# MCU.net
KiCad netlist of a schematic drawn in Altium Designer
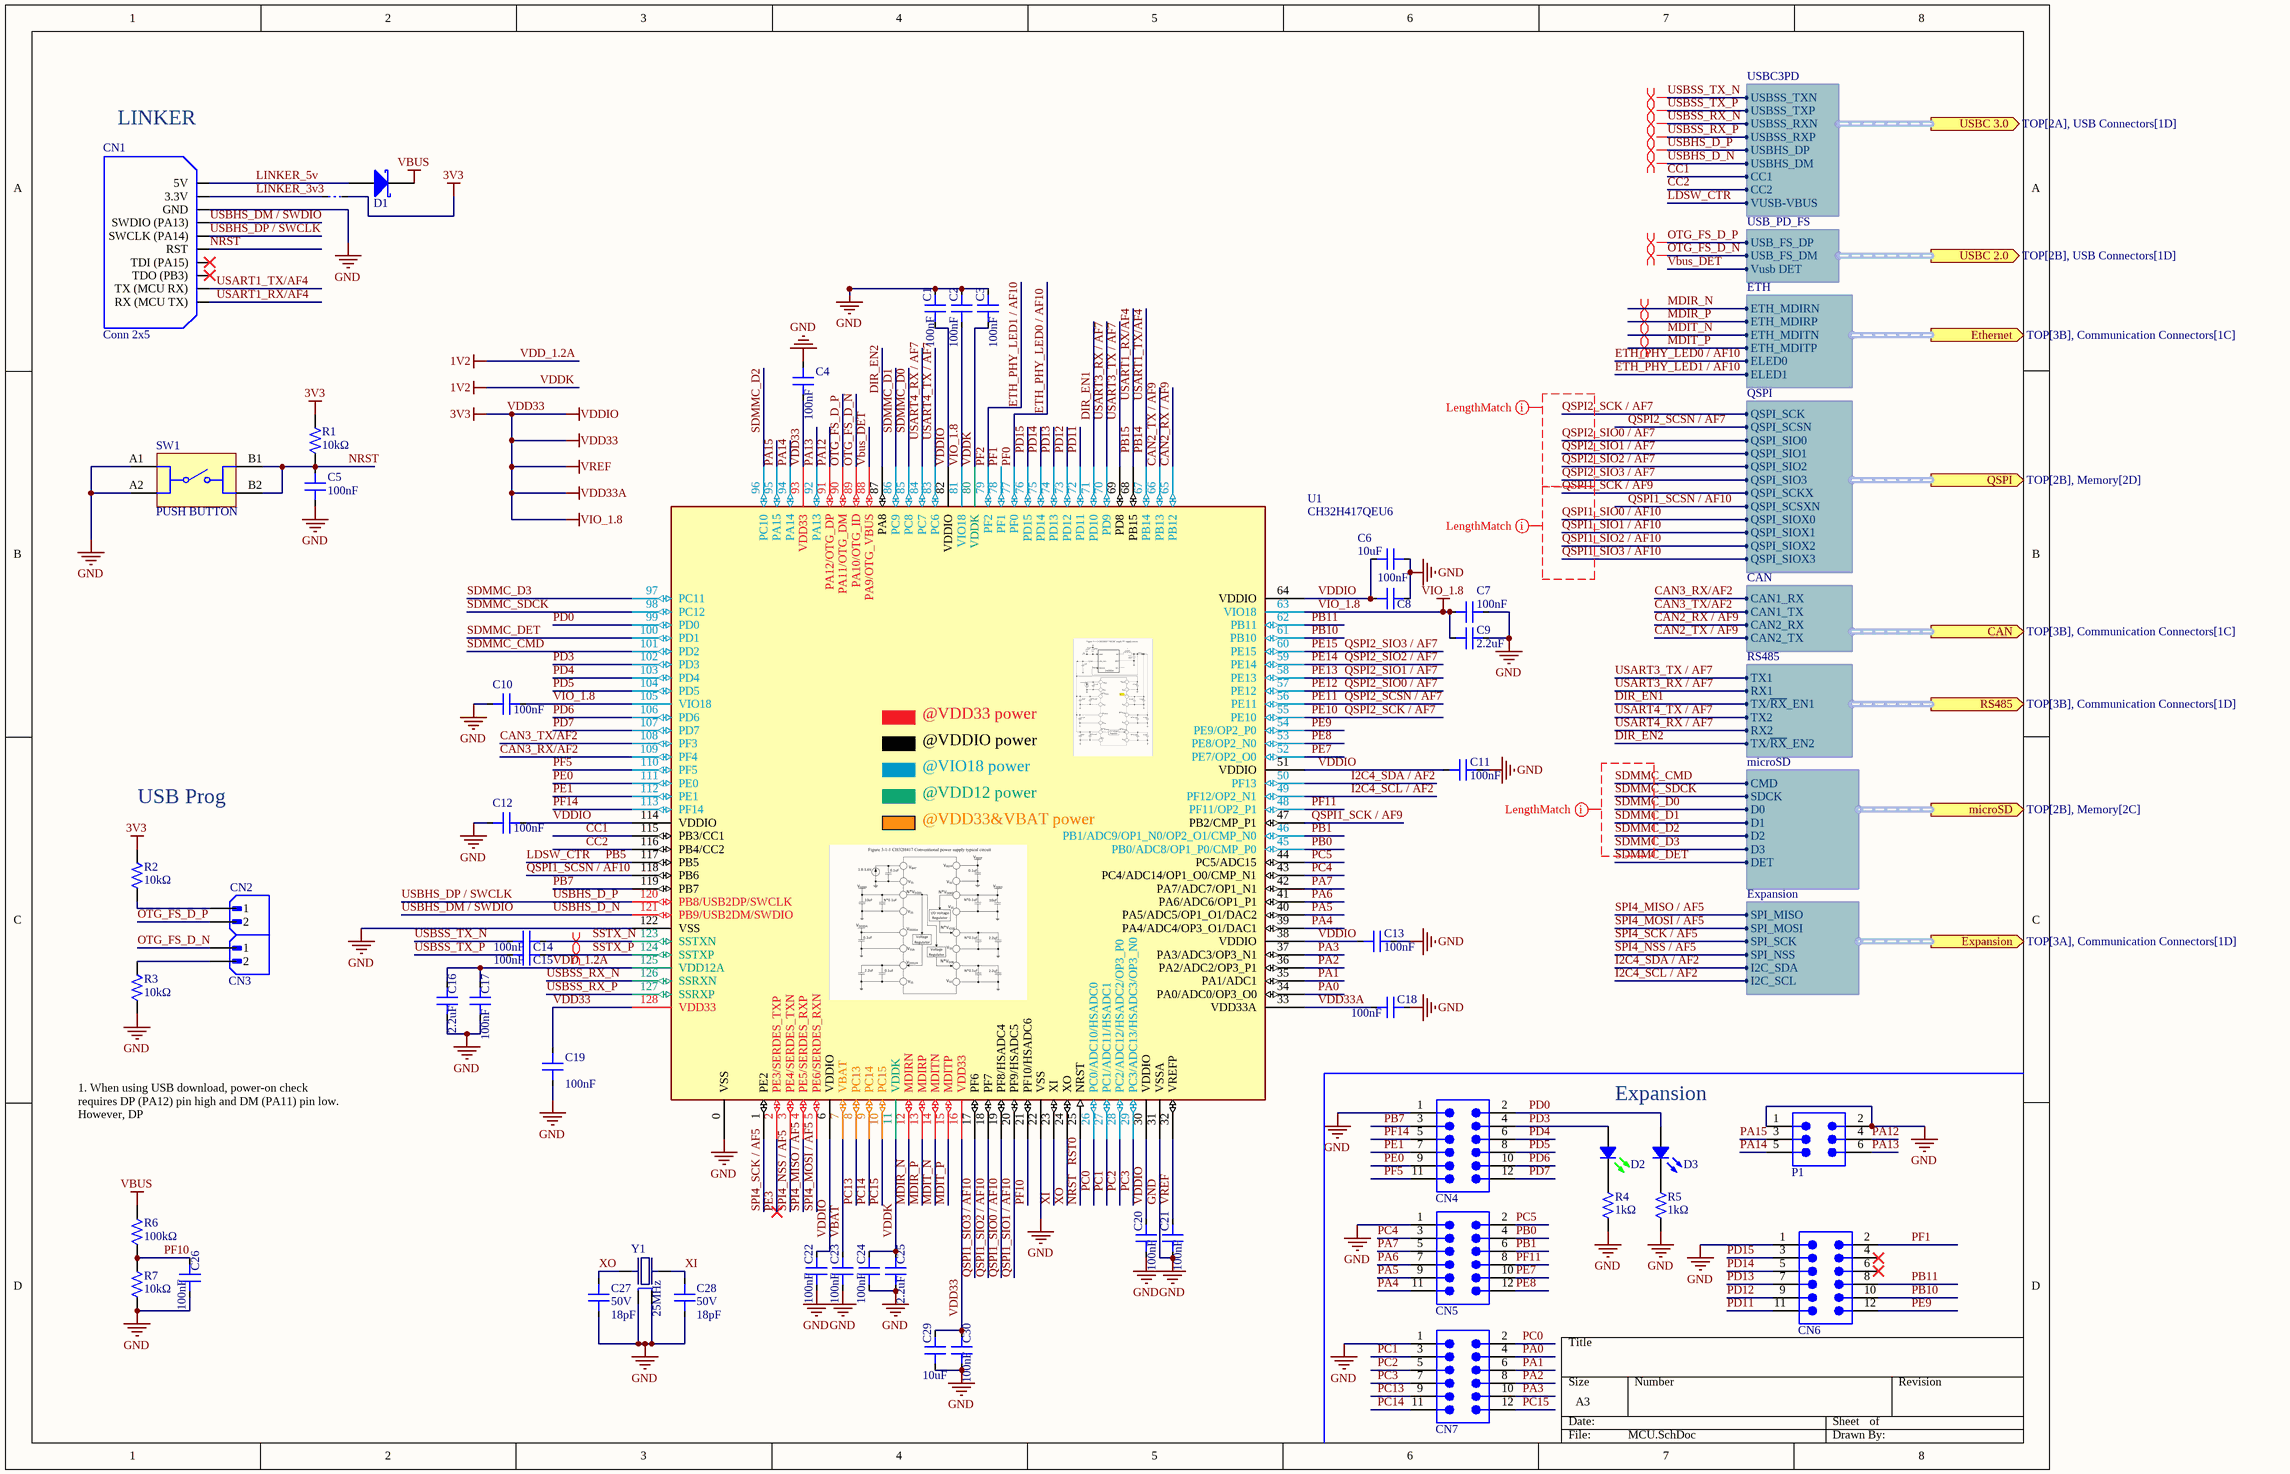
[diagram p0: MCU.SchDoc]

(export (version "E")
  (design (tool "Eeschema 10.0.6"))
  (components
    (comp (ref "C1")
      (value "CAP CER 100nF 50V X7R 0603")
      (footprint "C_0603")
      (description "100nF ±10% 50V Ceramic Capacitor X7R 0603")
      (fields
        (field (name "CAPACITANCE") "100nF")
        (field (name "MPN") "CC0603KRX7R9BB104")
        (field (name "LCSC PART #") "C14663")
      )
      (libsource (lib "Database_Libs_MICH_1") (part "CAP"))
    )
    (comp (ref "C2")
      (value "CAP CER 100nF 50V X7R 0603")
      (footprint "C_0603")
      (description "100nF ±10% 50V Ceramic Capacitor X7R 0603")
      (fields
        (field (name "CAPACITANCE") "100nF")
        (field (name "MPN") "CC0603KRX7R9BB104")
        (field (name "LCSC PART #") "C14663")
      )
      (libsource (lib "Database_Libs_MICH_1") (part "CAP"))
    )
    (comp (ref "C3")
      (value "CAP CER 100nF 50V X7R 0603")
      (footprint "C_0603")
      (description "100nF ±10% 50V Ceramic Capacitor X7R 0603")
      (fields
        (field (name "CAPACITANCE") "100nF")
        (field (name "MPN") "CC0603KRX7R9BB104")
        (field (name "LCSC PART #") "C14663")
      )
      (libsource (lib "Database_Libs_MICH_1") (part "CAP"))
    )
    (comp (ref "C4")
      (value "CAP CER 100nF 50V X7R 0603")
      (footprint "C_0603")
      (description "100nF ±10% 50V Ceramic Capacitor X7R 0603")
      (fields
        (field (name "CAPACITANCE") "100nF")
        (field (name "MPN") "CC0603KRX7R9BB104")
        (field (name "LCSC PART #") "C14663")
      )
      (libsource (lib "Database_Libs_MICH_1") (part "CAP"))
    )
    (comp (ref "C5")
      (value "CAP CER 100nF 50V X7R 0603")
      (footprint "C_0603")
      (description "100nF ±10% 50V Ceramic Capacitor X7R 0603")
      (fields
        (field (name "CAPACITANCE") "100nF")
        (field (name "MPN") "CC0603KRX7R9BB104")
        (field (name "LCSC PART #") "C14663")
      )
      (libsource (lib "Database_Libs_MICH_1") (part "CAP"))
    )
    (comp (ref "C6")
      (value "CAP CER 10uF 16V X7R 0805")
      (footprint "C_0805")
      (description "10uF ±10% 16V Ceramic Capacitor X7R 0805")
      (fields
        (field (name "CAPACITANCE") "10uF")
        (field (name "MPN") "CL21B106KOQNNNE")
        (field (name "LCSC PART #") "C95841")
      )
      (libsource (lib "Database_Libs_MICH_1") (part "CAP"))
    )
    (comp (ref "C7")
      (value "CAP CER 100nF 50V X7R 0603")
      (footprint "C_0603")
      (description "100nF ±10% 50V Ceramic Capacitor X7R 0603")
      (fields
        (field (name "CAPACITANCE") "100nF")
        (field (name "MPN") "CC0603KRX7R9BB104")
        (field (name "LCSC PART #") "C14663")
      )
      (libsource (lib "Database_Libs_MICH_1") (part "CAP"))
    )
    (comp (ref "C8")
      (value "CAP CER 100nF 50V X7R 0603")
      (footprint "C_0603")
      (description "100nF ±10% 50V Ceramic Capacitor X7R 0603")
      (fields
        (field (name "CAPACITANCE") "100nF")
        (field (name "MPN") "CC0603KRX7R9BB104")
        (field (name "LCSC PART #") "C14663")
      )
      (libsource (lib "Database_Libs_MICH_1") (part "CAP"))
    )
    (comp (ref "C9")
      (value "CAP CER 2.2uF 16V X5R 0603")
      (footprint "C_0603")
      (description "2.2uF ±10% 16V Ceramic Capacitor X5R 0603")
      (fields
        (field (name "CAPACITANCE") "2.2uF")
        (field (name "MPN") "CL10A225KO8NNNC")
        (field (name "LCSC PART #") "C23630")
      )
      (libsource (lib "Database_Libs_MICH_1") (part "CAP"))
    )
    (comp (ref "C10")
      (value "CAP CER 100nF 50V X7R 0603")
      (footprint "C_0603")
      (description "100nF ±10% 50V Ceramic Capacitor X7R 0603")
      (fields
        (field (name "CAPACITANCE") "100nF")
        (field (name "MPN") "CC0603KRX7R9BB104")
        (field (name "LCSC PART #") "C14663")
      )
      (libsource (lib "Database_Libs_MICH_1") (part "CAP"))
    )
    (comp (ref "C11")
      (value "CAP CER 100nF 50V X7R 0603")
      (footprint "C_0603")
      (description "100nF ±10% 50V Ceramic Capacitor X7R 0603")
      (fields
        (field (name "CAPACITANCE") "100nF")
        (field (name "MPN") "CC0603KRX7R9BB104")
        (field (name "LCSC PART #") "C14663")
      )
      (libsource (lib "Database_Libs_MICH_1") (part "CAP"))
    )
    (comp (ref "C12")
      (value "CAP CER 100nF 50V X7R 0603")
      (footprint "C_0603")
      (description "100nF ±10% 50V Ceramic Capacitor X7R 0603")
      (fields
        (field (name "CAPACITANCE") "100nF")
        (field (name "MPN") "CC0603KRX7R9BB104")
        (field (name "LCSC PART #") "C14663")
      )
      (libsource (lib "Database_Libs_MICH_1") (part "CAP"))
    )
    (comp (ref "C13")
      (value "CAP CER 100nF 50V X7R 0603")
      (footprint "C_0603")
      (description "100nF ±10% 50V Ceramic Capacitor X7R 0603")
      (fields
        (field (name "CAPACITANCE") "100nF")
        (field (name "MPN") "CC0603KRX7R9BB104")
        (field (name "LCSC PART #") "C14663")
      )
      (libsource (lib "Database_Libs_MICH_1") (part "CAP"))
    )
    (comp (ref "C14")
      (value "CAP CER 100nF 50V X7R 0603")
      (footprint "C_0603")
      (description "100nF ±10% 50V Ceramic Capacitor X7R 0603")
      (fields
        (field (name "CAPACITANCE") "100nF")
        (field (name "LCSC PART #") "C14663")
        (field (name "MANUFACTURER") "YAGEO")
      )
      (libsource (lib "Database_Libs_MICH_1") (part "CAP"))
    )
    (comp (ref "C15")
      (value "CAP CER 100nF 50V X7R 0603")
      (footprint "C_0603")
      (description "100nF ±10% 50V Ceramic Capacitor X7R 0603")
      (fields
        (field (name "CAPACITANCE") "100nF")
        (field (name "LCSC PART #") "C14663")
        (field (name "MANUFACTURER") "YAGEO")
      )
      (libsource (lib "Database_Libs_MICH_1") (part "CAP"))
    )
    (comp (ref "C16")
      (value "CAP CER 2.2uF 16V X5R 0603")
      (footprint "C_0603")
      (description "2.2uF ±10% 16V Ceramic Capacitor X5R 0603")
      (fields
        (field (name "CAPACITANCE") "2.2uF")
        (field (name "MPN") "CL10A225KO8NNNC")
        (field (name "LCSC PART #") "C23630")
      )
      (libsource (lib "Database_Libs_MICH_1") (part "CAP"))
    )
    (comp (ref "C17")
      (value "CAP CER 100nF 50V X7R 0603")
      (footprint "C_0603")
      (description "100nF ±10% 50V Ceramic Capacitor X7R 0603")
      (fields
        (field (name "CAPACITANCE") "100nF")
        (field (name "MPN") "CC0603KRX7R9BB104")
        (field (name "LCSC PART #") "C14663")
      )
      (libsource (lib "Database_Libs_MICH_1") (part "CAP"))
    )
    (comp (ref "C18")
      (value "CAP CER 100nF 50V X7R 0603")
      (footprint "C_0603")
      (description "100nF ±10% 50V Ceramic Capacitor X7R 0603")
      (fields
        (field (name "CAPACITANCE") "100nF")
        (field (name "MPN") "CC0603KRX7R9BB104")
        (field (name "LCSC PART #") "C14663")
      )
      (libsource (lib "Database_Libs_MICH_1") (part "CAP"))
    )
    (comp (ref "C19")
      (value "CAP CER 100nF 50V X7R 0603")
      (footprint "C_0603")
      (description "100nF ±10% 50V Ceramic Capacitor X7R 0603")
      (fields
        (field (name "CAPACITANCE") "100nF")
        (field (name "MPN") "CC0603KRX7R9BB104")
        (field (name "LCSC PART #") "C14663")
      )
      (libsource (lib "Database_Libs_MICH_1") (part "CAP"))
    )
    (comp (ref "C20")
      (value "CAP CER 100nF 50V X7R 0603")
      (footprint "C_0603")
      (description "100nF ±10% 50V Ceramic Capacitor X7R 0603")
      (fields
        (field (name "CAPACITANCE") "100nF")
        (field (name "MPN") "CC0603KRX7R9BB104")
        (field (name "LCSC PART #") "C14663")
      )
      (libsource (lib "Database_Libs_MICH_1") (part "CAP"))
    )
    (comp (ref "C21")
      (value "CAP CER 100nF 50V X7R 0603")
      (footprint "C_0603")
      (description "100nF ±10% 50V Ceramic Capacitor X7R 0603")
      (fields
        (field (name "CAPACITANCE") "100nF")
        (field (name "MPN") "CC0603KRX7R9BB104")
        (field (name "LCSC PART #") "C14663")
      )
      (libsource (lib "Database_Libs_MICH_1") (part "CAP"))
    )
    (comp (ref "C22")
      (value "CAP CER 100nF 50V X7R 0603")
      (footprint "C_0603")
      (description "100nF ±10% 50V Ceramic Capacitor X7R 0603")
      (fields
        (field (name "CAPACITANCE") "100nF")
        (field (name "MPN") "CC0603KRX7R9BB104")
        (field (name "LCSC PART #") "C14663")
      )
      (libsource (lib "Database_Libs_MICH_1") (part "CAP"))
    )
    (comp (ref "C23")
      (value "CAP CER 100nF 50V X7R 0603")
      (footprint "C_0603")
      (description "100nF ±10% 50V Ceramic Capacitor X7R 0603")
      (fields
        (field (name "CAPACITANCE") "100nF")
        (field (name "MPN") "CC0603KRX7R9BB104")
        (field (name "LCSC PART #") "C14663")
      )
      (libsource (lib "Database_Libs_MICH_1") (part "CAP"))
    )
    (comp (ref "C24")
      (value "CAP CER 100nF 50V X7R 0603")
      (footprint "C_0603")
      (description "100nF ±10% 50V Ceramic Capacitor X7R 0603")
      (fields
        (field (name "CAPACITANCE") "100nF")
        (field (name "MPN") "CC0603KRX7R9BB104")
        (field (name "LCSC PART #") "C14663")
      )
      (libsource (lib "Database_Libs_MICH_1") (part "CAP"))
    )
    (comp (ref "C25")
      (value "CAP CER 2.2uF 16V X5R 0603")
      (footprint "C_0603")
      (description "2.2uF ±10% 16V Ceramic Capacitor X5R 0603")
      (fields
        (field (name "CAPACITANCE") "2.2uF")
        (field (name "MPN") "CL10A225KO8NNNC")
        (field (name "LCSC PART #") "C23630")
      )
      (libsource (lib "Database_Libs_MICH_1") (part "CAP"))
    )
    (comp (ref "C26")
      (value "CAP CER 100nF 50V X7R 0603")
      (footprint "C_0603")
      (description "100nF ±10% 50V Ceramic Capacitor X7R 0603")
      (fields
        (field (name "CAPACITANCE") "100nF")
        (field (name "MPN") "CC0603KRX7R9BB104")
        (field (name "LCSC PART #") "C14663")
      )
      (libsource (lib "Database_Libs_MICH_1") (part "CAP"))
    )
    (comp (ref "C27")
      (value "CAP CER 18pF 50V C0G 0603")
      (footprint "C_0603")
      (description "18pF ±5% 50V Ceramic Capacitor C0G 0603")
      (fields
        (field (name "VOLTAGE RATING") "50V")
        (field (name "CAPACITANCE") "18pF")
        (field (name "LCSC PART #") "C1647")
        (field (name "MANUFACTURER") "Samsung Electro-Mechanics")
      )
      (libsource (lib "Database_Libs_MICH_1") (part "CAP"))
    )
    (comp (ref "C28")
      (value "CAP CER 18pF 50V C0G 0603")
      (footprint "C_0603")
      (description "18pF ±5% 50V Ceramic Capacitor C0G 0603")
      (fields
        (field (name "VOLTAGE RATING") "50V")
        (field (name "CAPACITANCE") "18pF")
        (field (name "LCSC PART #") "C1647")
        (field (name "MANUFACTURER") "Samsung Electro-Mechanics")
      )
      (libsource (lib "Database_Libs_MICH_1") (part "CAP"))
    )
    (comp (ref "C29")
      (value "CAP CER 10uF 16V X7R 0805")
      (footprint "C_0805")
      (description "10uF ±10% 16V Ceramic Capacitor X7R 0805")
      (fields
        (field (name "CAPACITANCE") "10uF")
        (field (name "MPN") "CL21B106KOQNNNE")
        (field (name "LCSC PART #") "C95841")
      )
      (libsource (lib "Database_Libs_MICH_1") (part "CAP"))
    )
    (comp (ref "C30")
      (value "CAP CER 100nF 50V X7R 0603")
      (footprint "C_0603")
      (description "100nF ±10% 50V Ceramic Capacitor X7R 0603")
      (fields
        (field (name "CAPACITANCE") "100nF")
        (field (name "MPN") "CC0603KRX7R9BB104")
        (field (name "LCSC PART #") "C14663")
      )
      (libsource (lib "Database_Libs_MICH_1") (part "CAP"))
    )
    (comp (ref "CN1")
      (value "Conn 2x5")
      (footprint "IDC_2x5P_2.54MM_TH")
      (description "CONN For WCH LINKE Debugger")
      (libsource (lib "MI_Personal_special") (part "WCH LINKE Debugger connector"))
    )
    (comp (ref "CN2")
      (value "CONN HEADER 2POS 2.54mm SINGLE ROW TH")
      (footprint "HEADER_M_2P_2.54MM_TH")
      (fields
        (field (name "MPN") "PZ254V-11-02P")
        (field (name "LCSC PART #") "C492401")
        (field (name "MANUFACTURER") "XFCN")
      )
      (libsource (lib "Database_Libs_MICH_1") (part "CONN_2"))
    )
    (comp (ref "CN3")
      (value "CONN HEADER 2POS 2.54mm SINGLE ROW TH")
      (footprint "HEADER_M_2P_2.54MM_TH")
      (fields
        (field (name "MPN") "PZ254V-11-02P")
        (field (name "LCSC PART #") "C492401")
        (field (name "MANUFACTURER") "XFCN")
      )
      (libsource (lib "Database_Libs_MICH_1") (part "CONN_2"))
    )
    (comp (ref "CN4")
      (value "CONN HEADER 12POS 2.54mm DUAL ROW TH")
      (footprint "HEADER_M_2x6P_2.54MM_TH")
      (description "Pin Header 12 Position 2.54mm Pitch Dual Row Through Hole -40℃~+105℃")
      (fields (field (name "MPN") "ZX-PZ2.54-2-6PZZ") (field (name "LCSC PART #") "C7501277"))
      (libsource (lib "Database_Libs_MICH_1") (part "CONN_2X6"))
    )
    (comp (ref "CN5")
      (value "CONN HEADER 12POS 2.54mm DUAL ROW TH")
      (footprint "HEADER_M_2x6P_2.54MM_TH")
      (description "Pin Header 12 Position 2.54mm Pitch Dual Row Through Hole -40℃~+105℃")
      (fields (field (name "MPN") "ZX-PZ2.54-2-6PZZ") (field (name "LCSC PART #") "C7501277"))
      (libsource (lib "Database_Libs_MICH_1") (part "CONN_2X6"))
    )
    (comp (ref "CN6")
      (value "CONN HEADER 12POS 2.54mm DUAL ROW TH")
      (footprint "HEADER_M_2x6P_2.54MM_TH")
      (description "Pin Header 12 Position 2.54mm Pitch Dual Row Through Hole -40℃~+105℃")
      (fields (field (name "MPN") "ZX-PZ2.54-2-6PZZ") (field (name "LCSC PART #") "C7501277"))
      (libsource (lib "Database_Libs_MICH_1") (part "CONN_2X6"))
    )
    (comp (ref "CN7")
      (value "CONN HEADER 12POS 2.54mm DUAL ROW TH")
      (footprint "HEADER_M_2x6P_2.54MM_TH")
      (description "Pin Header 12 Position 2.54mm Pitch Dual Row Through Hole -40℃~+105℃")
      (fields (field (name "MPN") "ZX-PZ2.54-2-6PZZ") (field (name "LCSC PART #") "C7501277"))
      (libsource (lib "Database_Libs_MICH_1") (part "CONN_2X6"))
    )
    (comp (ref "D1")
      (value "DIODE SCHOTTKY 40V SOD-323")
      (footprint "SOD323")
      (description "Diode 40V 1A Surface Mount SOD-323")
      (fields (field (name "MPN") "1N5819WS") (field (name "LCSC PART #") "C191023"))
      (libsource (lib "Database_Libs_MICH_1") (part "DIODE_SCHOTTKY"))
    )
    (comp (ref "D2")
      (value "LED EMERALD GREEN WATER CLEAR 0603 SMD")
      (footprint "LED_0603")
      (description "Emerald Green 525nm LED Indication - Discrete 3.3V 0603")
      (fields (field (name "MPN") "XL-1608UGC-04") (field (name "LCSC PART #") "C965804"))
      (libsource (lib "Database_Libs_MICH_1") (part "LED_EMERALD GREEN"))
    )
    (comp (ref "D3")
      (value "LED BLUE WATER CLEAR 0603 SMD")
      (footprint "LED_0603")
      (description "Blue 470nm LED Indication - Discrete 3.3V 0603")
      (fields (field (name "MPN") "XL-1608UBC-04") (field (name "LCSC PART #") "C965807"))
      (libsource (lib "Database_Libs_MICH_1") (part "LED_BLUE"))
    )
    (comp (ref "J1")
      (value "JUMPER SMD")
      (footprint "JUMPER SMD 3X1.5 mm")
      (libsource (lib "MI_Personal_special") (part "JUMPER SMD"))
    )
    (comp (ref "P1")
      (value "CONN SOCKET 6POS 2.54mm DUAL ROW TH")
      (footprint "HEADER_F_2x3P_2.54MM_TH")
      (description "Female Header 6 Position 2.54mm Pitch Dual Row Through Hole")
      (fields (field (name "MPN") "PM254V-12-06-H85") (field (name "LCSC PART #") "C541853"))
      (libsource (lib "Database_Libs_MICH_1") (part "CONN_2x3"))
    )
    (comp (ref "R1")
      (value "RES 10kΩ ±1% 100mW 0603")
      (footprint "R_0603")
      (description "10kΩ ±1% 100mW 0603 Thick Film Resistor")
      (fields
        (field (name "RESISTANCE") "10kΩ")
        (field (name "MPN") "0603WAF1002T5E")
        (field (name "POWER") "100mW")
      )
      (libsource (lib "Database_Libs_MICH_1") (part "RES"))
    )
    (comp (ref "R2")
      (value "RES 10kΩ ±1% 100mW 0603")
      (footprint "R_0603")
      (description "10kΩ ±1% 100mW 0603 Thick Film Resistor")
      (fields
        (field (name "RESISTANCE") "10kΩ")
        (field (name "MPN") "0603WAF1002T5E")
        (field (name "POWER") "100mW")
      )
      (libsource (lib "Database_Libs_MICH_1") (part "RES"))
    )
    (comp (ref "R3")
      (value "RES 10kΩ ±1% 100mW 0603")
      (footprint "R_0603")
      (description "10kΩ ±1% 100mW 0603 Thick Film Resistor")
      (fields
        (field (name "RESISTANCE") "10kΩ")
        (field (name "MPN") "0603WAF1002T5E")
        (field (name "POWER") "100mW")
      )
      (libsource (lib "Database_Libs_MICH_1") (part "RES"))
    )
    (comp (ref "R4")
      (value "RES 1kΩ ±1% 100mW 0603")
      (footprint "R_0603")
      (description "1kΩ ±1% 100mW 0603 Thick Film Resistor")
      (fields
        (field (name "RESISTANCE") "1kΩ")
        (field (name "MPN") "0603WAF1001T5E")
        (field (name "POWER") "100mW")
      )
      (libsource (lib "Database_Libs_MICH_1") (part "RES"))
    )
    (comp (ref "R5")
      (value "RES 1kΩ ±1% 100mW 0603")
      (footprint "R_0603")
      (description "1kΩ ±1% 100mW 0603 Thick Film Resistor")
      (fields
        (field (name "RESISTANCE") "1kΩ")
        (field (name "MPN") "0603WAF1001T5E")
        (field (name "POWER") "100mW")
      )
      (libsource (lib "Database_Libs_MICH_1") (part "RES"))
    )
    (comp (ref "R6")
      (value "RES 100kΩ ±1% 100mW 0603")
      (footprint "R_0603")
      (description "100kΩ ±1% 100mW 0603 Thick Film Resistor")
      (fields
        (field (name "RESISTANCE") "100kΩ")
        (field (name "LCSC PART #") "C25803")
        (field (name "MPN") "0603WAF1003T5E")
      )
      (libsource (lib "Database_Libs_MICH_1") (part "RES"))
    )
    (comp (ref "R7")
      (value "RES 10kΩ ±1% 100mW 0603")
      (footprint "R_0603")
      (description "10kΩ ±1% 100mW 0603 Thick Film Resistor")
      (fields
        (field (name "RESISTANCE") "10kΩ")
        (field (name "MPN") "0603WAF1002T5E")
        (field (name "POWER") "100mW")
      )
      (libsource (lib "Database_Libs_MICH_1") (part "RES"))
    )
    (comp (ref "SW1")
      (value "PUSH BUTTON")
      (footprint "Tact Switch 6X6X9.5MM")
      (description "SWITCH PUSH BUTTON 2X2 6X6X9.5MM")
      (libsource (lib "MI_Personal_special") (part "SH-6X6X8H-CJ"))
    )
    (comp (ref "U1")
      (value "CH32H417QEU6")
      (footprint "QFN128_12.3X12.3")
      (description "RISC-V FPU HD-MCU, 384MHz, USB3.0 & PD, 100M Ethernet, DVP, SDMMC, QSPI, OPA, ADC, DAC")
      (libsource (lib "DHXXXSCH") (part "CH32H417QET6"))
    )
    (comp (ref "Y1")
      (value "CRYSTAL 25MHz 12pF SMD")
      (footprint "XTAL_SMD3225-4P")
      (description "Crystal 25MHz ±10ppm 12pF SMD3225-4P")
      (fields
        (field (name "FREQUENCY") "25MHz")
        (field (name "MPN") "X322525MOB4SI")
        (field (name "LCSC PART #") "C9006")
      )
      (libsource (lib "Database_Libs_MICH_1") (part "XTAL-4P"))
    )
  )
  (nets
    (net (code "9") (name "/CAN2_RX {slash} AF9") (class "Default")
      (node (ref "U1") (pin "65") (pinfunction "PB12_65") (pintype "bidirectional"))
    )
    (net (code "10") (name "/CAN2_TX {slash} AF9") (class "Default")
      (node (ref "U1") (pin "66") (pinfunction "PB13_66") (pintype "bidirectional"))
    )
    (net (code "11") (name "/CAN3_RX{slash}AF2") (class "Default")
      (node (ref "U1") (pin "109") (pinfunction "PF4_109") (pintype "bidirectional"))
    )
    (net (code "12") (name "/CAN3_TX{slash}AF2") (class "Default")
      (node (ref "U1") (pin "108") (pinfunction "PF3_108") (pintype "bidirectional"))
    )
    (net (code "13") (name "/CC1") (class "Default")
      (node (ref "U1") (pin "115") (pinfunction "PB3/CC1_115") (pintype "bidirectional"))
    )
    (net (code "14") (name "/CC2") (class "Default")
      (node (ref "U1") (pin "116") (pinfunction "PB4/CC2_116") (pintype "bidirectional"))
    )
    (net (code "15") (name "/DIR_EN1") (class "Default")
      (node (ref "U1") (pin "71") (pinfunction "PD10_71") (pintype "bidirectional"))
    )
    (net (code "16") (name "/DIR_EN2") (class "Default")
      (node (ref "U1") (pin "87") (pinfunction "PA8_87") (pintype "bidirectional"))
    )
    (net (code "17") (name "/ETH_PHY_LED0 {slash} AF10") (class "Default")
      (node (ref "U1") (pin "77") (pinfunction "PF0_77") (pintype "bidirectional"))
    )
    (net (code "18") (name "/ETH_PHY_LED1 {slash} AF10") (class "Default")
      (node (ref "U1") (pin "79") (pinfunction "PF2_79") (pintype "bidirectional"))
    )
    (net (code "19") (name "/I2C4_SCL {slash} AF2") (class "Default")
      (node (ref "U1") (pin "49") (pinfunction "PF12/OP2_N1_49") (pintype "bidirectional"))
    )
    (net (code "20") (name "/I2C4_SDA {slash} AF2") (class "Default")
      (node (ref "U1") (pin "50") (pinfunction "PF13_50") (pintype "bidirectional"))
    )
    (net (code "21") (name "/LDSW_CTR") (class "Default")
      (node (ref "U1") (pin "117") (pinfunction "PB5_117") (pintype "bidirectional"))
    )
    (net (code "22") (name "/LINKER_3v3") (class "Default")
      (node (ref "CN1") (pin "3") (pinfunction "3.3V_3") (pintype "passive"))
      (node (ref "J1") (pin "2") (pinfunction "G_2") (pintype "passive"))
    )
    (net (code "23") (name "/LINKER_5v") (class "Default")
      (node (ref "CN1") (pin "1") (pinfunction "5V_1") (pintype "passive"))
      (node (ref "D1") (pin "1") (pinfunction "A_1") (pintype "passive"))
    )
    (net (code "24") (name "/MDIR_N") (class "Default")
      (node (ref "U1") (pin "12") (pinfunction "MDIRN_12") (pintype "bidirectional"))
    )
    (net (code "25") (name "/MDIR_P") (class "Default")
      (node (ref "U1") (pin "13") (pinfunction "MDIRP_13") (pintype "bidirectional"))
    )
    (net (code "26") (name "/MDIT_N") (class "Default")
      (node (ref "U1") (pin "14") (pinfunction "MDITN_14") (pintype "bidirectional"))
    )
    (net (code "27") (name "/MDIT_P") (class "Default")
      (node (ref "U1") (pin "15") (pinfunction "MDITP_15") (pintype "bidirectional"))
    )
    (net (code "28") (name "/NRST") (class "Default")
      (node (ref "C5") (pin "2") (pinfunction "2_2") (pintype "passive"))
      (node (ref "CN1") (pin "2") (pinfunction "RST_2") (pintype "passive"))
      (node (ref "R1") (pin "1") (pinfunction "1_1") (pintype "passive"))
      (node (ref "SW1") (pin "B1") (pinfunction "B1_B1") (pintype "passive"))
      (node (ref "SW1") (pin "B2") (pinfunction "B2_B2") (pintype "passive"))
      (node (ref "U1") (pin "25") (pinfunction "NRST_25") (pintype "input"))
    )
    (net (code "29") (name "/OTG_FS_D_N") (class "Default")
      (node (ref "CN3") (pin "1") (pinfunction "1_1") (pintype "passive"))
      (node (ref "U1") (pin "89") (pinfunction "PA10/OTG_ID_89") (pintype "bidirectional"))
    )
    (net (code "30") (name "/OTG_FS_D_P") (class "Default")
      (node (ref "CN2") (pin "2") (pinfunction "2_2") (pintype "passive"))
      (node (ref "U1") (pin "90") (pinfunction "PA11/OTG_DM_90") (pintype "bidirectional"))
    )
    (net (code "31") (name "/PA0") (class "Default")
      (node (ref "CN7") (pin "4") (pinfunction "4_4") (pintype "passive"))
      (node (ref "U1") (pin "34") (pinfunction "PA0/ADC0/OP3_O0_34") (pintype "bidirectional"))
    )
    (net (code "32") (name "/PA1") (class "Default")
      (node (ref "CN7") (pin "6") (pinfunction "6_6") (pintype "passive"))
      (node (ref "U1") (pin "35") (pinfunction "PA1/ADC1_35") (pintype "bidirectional"))
    )
    (net (code "33") (name "/PA2") (class "Default")
      (node (ref "CN7") (pin "8") (pinfunction "8_8") (pintype "passive"))
      (node (ref "U1") (pin "36") (pinfunction "PA2/ADC2/OP3_P1_36") (pintype "bidirectional"))
    )
    (net (code "34") (name "/PA3") (class "Default")
      (node (ref "CN7") (pin "10") (pinfunction "10_10") (pintype "passive"))
      (node (ref "U1") (pin "37") (pinfunction "PA3/ADC3/OP3_N1_37") (pintype "bidirectional"))
    )
    (net (code "35") (name "/PA4") (class "Default")
      (node (ref "CN5") (pin "11") (pinfunction "11_11") (pintype "passive"))
      (node (ref "U1") (pin "39") (pinfunction "PA4/ADC4/OP3_O1/DAC1_39") (pintype "bidirectional"))
    )
    (net (code "36") (name "/PA5") (class "Default")
      (node (ref "CN5") (pin "9") (pinfunction "9_9") (pintype "passive"))
      (node (ref "U1") (pin "40") (pinfunction "PA5/ADC5/OP1_O1/DAC2_40") (pintype "bidirectional"))
    )
    (net (code "37") (name "/PA6") (class "Default")
      (node (ref "CN5") (pin "7") (pinfunction "7_7") (pintype "passive"))
      (node (ref "U1") (pin "41") (pinfunction "PA6/ADC6/OP1_P1_41") (pintype "bidirectional"))
    )
    (net (code "38") (name "/PA7") (class "Default")
      (node (ref "CN5") (pin "5") (pinfunction "5_5") (pintype "passive"))
      (node (ref "U1") (pin "42") (pinfunction "PA7/ADC7/OP1_N1_42") (pintype "bidirectional"))
    )
    (net (code "39") (name "/PA12") (class "Default")
      (node (ref "P1") (pin "4") (pinfunction "4_4") (pintype "passive"))
      (node (ref "U1") (pin "91") (pinfunction "PA12/OTG_DP_91") (pintype "bidirectional"))
    )
    (net (code "40") (name "/PA13") (class "Default")
      (node (ref "P1") (pin "6") (pinfunction "6_6") (pintype "passive"))
      (node (ref "U1") (pin "92") (pinfunction "PA13_92") (pintype "bidirectional"))
    )
    (net (code "41") (name "/PA14") (class "Default")
      (node (ref "P1") (pin "5") (pinfunction "5_5") (pintype "passive"))
      (node (ref "U1") (pin "94") (pinfunction "PA14_94") (pintype "bidirectional"))
    )
    (net (code "42") (name "/PA15") (class "Default")
      (node (ref "P1") (pin "3") (pinfunction "3_3") (pintype "passive"))
      (node (ref "U1") (pin "95") (pinfunction "PA15_95") (pintype "bidirectional"))
    )
    (net (code "43") (name "/PB0") (class "Default")
      (node (ref "CN5") (pin "4") (pinfunction "4_4") (pintype "passive"))
      (node (ref "U1") (pin "45") (pinfunction "PB0/ADC8/OP1_P0/CMP_P0_45") (pintype "bidirectional"))
    )
    (net (code "44") (name "/PB1") (class "Default")
      (node (ref "CN5") (pin "6") (pinfunction "6_6") (pintype "passive"))
      (node (ref "U1") (pin "46") (pinfunction "PB1/ADC9/OP1_N0/OP2_O1/CMP_N0_46") (pintype "bidirectional"))
    )
    (net (code "45") (name "/PB7") (class "Default")
      (node (ref "CN4") (pin "3") (pinfunction "3_3") (pintype "passive"))
      (node (ref "U1") (pin "119") (pinfunction "PB7_119") (pintype "bidirectional"))
    )
    (net (code "46") (name "/PB10") (class "Default")
      (node (ref "CN6") (pin "10") (pinfunction "10_10") (pintype "passive"))
      (node (ref "U1") (pin "61") (pinfunction "PB10_61") (pintype "bidirectional"))
    )
    (net (code "47") (name "/PB11") (class "Default")
      (node (ref "CN6") (pin "8") (pinfunction "8_8") (pintype "passive"))
      (node (ref "U1") (pin "62") (pinfunction "PB11_62") (pintype "bidirectional"))
    )
    (net (code "48") (name "/PB14") (class "Default")
      (node (ref "CN1") (pin "8") (pinfunction "TX_(MCU_RX)_8") (pintype "passive"))
      (node (ref "U1") (pin "67") (pinfunction "PB14_67") (pintype "bidirectional"))
    )
    (net (code "49") (name "/PB15") (class "Default")
      (node (ref "CN1") (pin "10") (pinfunction "RX_(MCU_TX)_10") (pintype "passive"))
      (node (ref "U1") (pin "68") (pinfunction "PB15_68") (pintype "bidirectional"))
    )
    (net (code "50") (name "/PC0") (class "Default")
      (node (ref "CN7") (pin "2") (pinfunction "2_2") (pintype "passive"))
      (node (ref "U1") (pin "26") (pinfunction "PC0/ADC10/HSADC0_26") (pintype "bidirectional"))
    )
    (net (code "51") (name "/PC1") (class "Default")
      (node (ref "CN7") (pin "3") (pinfunction "3_3") (pintype "passive"))
      (node (ref "U1") (pin "27") (pinfunction "PC1/ADC11/HSADC1_27") (pintype "bidirectional"))
    )
    (net (code "52") (name "/PC2") (class "Default")
      (node (ref "CN7") (pin "5") (pinfunction "5_5") (pintype "passive"))
      (node (ref "U1") (pin "28") (pinfunction "PC2/ADC12/HSADC2/OP3_P0_28") (pintype "bidirectional"))
    )
    (net (code "53") (name "/PC3") (class "Default")
      (node (ref "CN7") (pin "7") (pinfunction "7_7") (pintype "passive"))
      (node (ref "U1") (pin "29") (pinfunction "PC3/ADC13/HSADC3/OP3_N0_29") (pintype "bidirectional"))
    )
    (net (code "54") (name "/PC4") (class "Default")
      (node (ref "CN5") (pin "3") (pinfunction "3_3") (pintype "passive"))
      (node (ref "U1") (pin "43") (pinfunction "PC4/ADC14/OP1_O0/CMP_N1_43") (pintype "bidirectional"))
    )
    (net (code "55") (name "/PC5") (class "Default")
      (node (ref "CN5") (pin "2") (pinfunction "2_2") (pintype "passive"))
      (node (ref "U1") (pin "44") (pinfunction "PC5/ADC15_44") (pintype "bidirectional"))
    )
    (net (code "56") (name "/PC13") (class "Default")
      (node (ref "CN7") (pin "9") (pinfunction "9_9") (pintype "passive"))
      (node (ref "U1") (pin "8") (pinfunction "PC13_8") (pintype "bidirectional"))
    )
    (net (code "57") (name "/PC14") (class "Default")
      (node (ref "CN7") (pin "11") (pinfunction "11_11") (pintype "passive"))
      (node (ref "U1") (pin "9") (pinfunction "PC14_9") (pintype "bidirectional"))
    )
    (net (code "58") (name "/PC15") (class "Default")
      (node (ref "CN7") (pin "12") (pinfunction "12_12") (pintype "passive"))
      (node (ref "U1") (pin "10") (pinfunction "PC15_10") (pintype "bidirectional"))
    )
    (net (code "59") (name "/PD0") (class "Default")
      (node (ref "CN4") (pin "2") (pinfunction "2_2") (pintype "passive"))
      (node (ref "D3") (pin "1") (pinfunction "1_1") (pintype "passive"))
      (node (ref "U1") (pin "99") (pinfunction "PD0_99") (pintype "bidirectional"))
    )
    (net (code "60") (name "/PD3") (class "Default")
      (node (ref "CN4") (pin "4") (pinfunction "4_4") (pintype "passive"))
      (node (ref "D2") (pin "1") (pinfunction "1_1") (pintype "passive"))
      (node (ref "U1") (pin "102") (pinfunction "PD3_102") (pintype "bidirectional"))
    )
    (net (code "61") (name "/PD4") (class "Default")
      (node (ref "CN4") (pin "6") (pinfunction "6_6") (pintype "passive"))
      (node (ref "U1") (pin "103") (pinfunction "PD4_103") (pintype "bidirectional"))
    )
    (net (code "62") (name "/PD5") (class "Default")
      (node (ref "CN4") (pin "8") (pinfunction "8_8") (pintype "passive"))
      (node (ref "U1") (pin "104") (pinfunction "PD5_104") (pintype "bidirectional"))
    )
    (net (code "63") (name "/PD6") (class "Default")
      (node (ref "CN4") (pin "10") (pinfunction "10_10") (pintype "passive"))
      (node (ref "U1") (pin "106") (pinfunction "PD6_106") (pintype "bidirectional"))
    )
    (net (code "64") (name "/PD7") (class "Default")
      (node (ref "CN4") (pin "12") (pinfunction "12_12") (pintype "passive"))
      (node (ref "U1") (pin "107") (pinfunction "PD7_107") (pintype "bidirectional"))
    )
    (net (code "65") (name "/PD11") (class "Default")
      (node (ref "CN6") (pin "11") (pinfunction "11_11") (pintype "passive"))
      (node (ref "U1") (pin "72") (pinfunction "PD11_72") (pintype "bidirectional"))
    )
    (net (code "66") (name "/PD12") (class "Default")
      (node (ref "CN6") (pin "9") (pinfunction "9_9") (pintype "passive"))
      (node (ref "U1") (pin "73") (pinfunction "PD12_73") (pintype "bidirectional"))
    )
    (net (code "67") (name "/PD13") (class "Default")
      (node (ref "CN6") (pin "7") (pinfunction "7_7") (pintype "passive"))
      (node (ref "U1") (pin "74") (pinfunction "PD13_74") (pintype "bidirectional"))
    )
    (net (code "68") (name "/PD14") (class "Default")
      (node (ref "CN6") (pin "5") (pinfunction "5_5") (pintype "passive"))
      (node (ref "U1") (pin "75") (pinfunction "PD14_75") (pintype "bidirectional"))
    )
    (net (code "69") (name "/PD15") (class "Default")
      (node (ref "CN6") (pin "3") (pinfunction "3_3") (pintype "passive"))
      (node (ref "U1") (pin "76") (pinfunction "PD15_76") (pintype "bidirectional"))
    )
    (net (code "70") (name "/PE0") (class "Default")
      (node (ref "CN4") (pin "9") (pinfunction "9_9") (pintype "passive"))
      (node (ref "U1") (pin "111") (pinfunction "PE0_111") (pintype "bidirectional"))
    )
    (net (code "71") (name "/PE1") (class "Default")
      (node (ref "CN4") (pin "7") (pinfunction "7_7") (pintype "passive"))
      (node (ref "U1") (pin "112") (pinfunction "PE1_112") (pintype "bidirectional"))
    )
    (net (code "72") (name "/PE3") (class "Default")
      (node (ref "U1") (pin "2") (pinfunction "PE3/SERDES_TXP_2") (pintype "bidirectional+no_connect"))
    )
    (net (code "73") (name "/PE7") (class "Default")
      (node (ref "CN5") (pin "10") (pinfunction "10_10") (pintype "passive"))
      (node (ref "U1") (pin "52") (pinfunction "PE7/OP2_O0_52") (pintype "bidirectional"))
    )
    (net (code "74") (name "/PE8") (class "Default")
      (node (ref "CN5") (pin "12") (pinfunction "12_12") (pintype "passive"))
      (node (ref "U1") (pin "53") (pinfunction "PE8/OP2_N0_53") (pintype "bidirectional"))
    )
    (net (code "75") (name "/PE9") (class "Default")
      (node (ref "CN6") (pin "12") (pinfunction "12_12") (pintype "passive"))
      (node (ref "U1") (pin "54") (pinfunction "PE9/OP2_P0_54") (pintype "bidirectional"))
    )
    (net (code "76") (name "/PE10") (class "Default")
      (node (ref "U1") (pin "55") (pinfunction "PE10_55") (pintype "bidirectional"))
    )
    (net (code "77") (name "/PE11") (class "Default")
      (node (ref "U1") (pin "56") (pinfunction "PE11_56") (pintype "bidirectional"))
    )
    (net (code "78") (name "/PE12") (class "Default")
      (node (ref "U1") (pin "57") (pinfunction "PE12_57") (pintype "bidirectional"))
    )
    (net (code "79") (name "/PE13") (class "Default")
      (node (ref "U1") (pin "58") (pinfunction "PE13_58") (pintype "bidirectional"))
    )
    (net (code "80") (name "/PE14") (class "Default")
      (node (ref "U1") (pin "59") (pinfunction "PE14_59") (pintype "bidirectional"))
    )
    (net (code "81") (name "/PE15") (class "Default")
      (node (ref "U1") (pin "60") (pinfunction "PE15_60") (pintype "bidirectional"))
    )
    (net (code "82") (name "/PF1") (class "Default")
      (node (ref "CN6") (pin "2") (pinfunction "2_2") (pintype "passive"))
      (node (ref "U1") (pin "78") (pinfunction "PF1_78") (pintype "bidirectional"))
    )
    (net (code "83") (name "/PF5") (class "Default")
      (node (ref "CN4") (pin "11") (pinfunction "11_11") (pintype "passive"))
      (node (ref "U1") (pin "110") (pinfunction "PF5_110") (pintype "bidirectional"))
    )
    (net (code "84") (name "/PF10") (class "Default")
      (node (ref "C26") (pin "1") (pinfunction "1_1") (pintype "passive"))
      (node (ref "R6") (pin "1") (pinfunction "1_1") (pintype "passive"))
      (node (ref "R7") (pin "1") (pinfunction "1_1") (pintype "passive"))
      (node (ref "U1") (pin "21") (pinfunction "PF10/HSADC6_21") (pintype "bidirectional"))
    )
    (net (code "85") (name "/PF11") (class "Default")
      (node (ref "CN5") (pin "8") (pinfunction "8_8") (pintype "passive"))
      (node (ref "U1") (pin "48") (pinfunction "PF11/OP2_P1_48") (pintype "bidirectional"))
    )
    (net (code "86") (name "/PF14") (class "Default")
      (node (ref "CN4") (pin "5") (pinfunction "5_5") (pintype "passive"))
      (node (ref "U1") (pin "113") (pinfunction "PF14_113") (pintype "bidirectional"))
    )
    (net (code "87") (name "/QSPI1_SCK {slash} AF9") (class "Default")
      (node (ref "U1") (pin "47") (pinfunction "PB2/CMP_P1_47") (pintype "bidirectional"))
    )
    (net (code "88") (name "/QSPI1_SCSN {slash} AF10") (class "Default")
      (node (ref "U1") (pin "118") (pinfunction "PB6_118") (pintype "bidirectional"))
    )
    (net (code "89") (name "/QSPI1_SIO0 {slash} AF10") (class "Default")
      (node (ref "U1") (pin "19") (pinfunction "PF8/HSADC4_19") (pintype "bidirectional"))
    )
    (net (code "90") (name "/QSPI1_SIO1 {slash} AF10") (class "Default")
      (node (ref "U1") (pin "20") (pinfunction "PF9/HSADC5_20") (pintype "bidirectional"))
    )
    (net (code "91") (name "/QSPI1_SIO2 {slash} AF10") (class "Default")
      (node (ref "U1") (pin "18") (pinfunction "PF7_18") (pintype "bidirectional"))
    )
    (net (code "92") (name "/QSPI1_SIO3 {slash} AF10") (class "Default")
      (node (ref "U1") (pin "17") (pinfunction "PF6_17") (pintype "bidirectional"))
    )
    (net (code "93") (name "/SDMMC_CMD") (class "Default")
      (node (ref "U1") (pin "101") (pinfunction "PD2_101") (pintype "bidirectional"))
    )
    (net (code "94") (name "/SDMMC_D0") (class "Default")
      (node (ref "U1") (pin "85") (pinfunction "PC8_85") (pintype "bidirectional"))
    )
    (net (code "95") (name "/SDMMC_D1") (class "Default")
      (node (ref "U1") (pin "86") (pinfunction "PC9_86") (pintype "bidirectional"))
    )
    (net (code "96") (name "/SDMMC_D2") (class "Default")
      (node (ref "U1") (pin "96") (pinfunction "PC10_96") (pintype "bidirectional"))
    )
    (net (code "97") (name "/SDMMC_D3") (class "Default")
      (node (ref "U1") (pin "97") (pinfunction "PC11_97") (pintype "bidirectional"))
    )
    (net (code "98") (name "/SDMMC_DET") (class "Default")
      (node (ref "U1") (pin "100") (pinfunction "PD1_100") (pintype "bidirectional"))
    )
    (net (code "99") (name "/SDMMC_SDCK") (class "Default")
      (node (ref "U1") (pin "98") (pinfunction "PC12_98") (pintype "bidirectional"))
    )
    (net (code "100") (name "/SPI4_MISO {slash} AF5") (class "Default")
      (node (ref "U1") (pin "4") (pinfunction "PE5/SERDES_RXP_4") (pintype "bidirectional"))
    )
    (net (code "101") (name "/SPI4_MOSI {slash} AF5") (class "Default")
      (node (ref "U1") (pin "5") (pinfunction "PE6/SERDES_RXN_5") (pintype "bidirectional"))
    )
    (net (code "102") (name "/SPI4_NSS {slash} AF5") (class "Default")
      (node (ref "U1") (pin "3") (pinfunction "PE4/SERDES_TXN_3") (pintype "bidirectional"))
    )
    (net (code "103") (name "/SPI4_SCK {slash} AF5") (class "Default")
      (node (ref "U1") (pin "1") (pinfunction "PE2_1") (pintype "bidirectional"))
    )
    (net (code "104") (name "/SSTX_N") (class "Default")
      (node (ref "C14") (pin "1") (pinfunction "1_1") (pintype "passive"))
      (node (ref "U1") (pin "123") (pinfunction "SSTXN_123") (pintype "bidirectional"))
    )
    (net (code "105") (name "/SSTX_P") (class "Default")
      (node (ref "C15") (pin "1") (pinfunction "1_1") (pintype "passive"))
      (node (ref "U1") (pin "124") (pinfunction "SSTXP_124") (pintype "bidirectional"))
    )
    (net (code "106") (name "/USART3_RX {slash} AF7") (class "Default")
      (node (ref "U1") (pin "70") (pinfunction "PD9_70") (pintype "bidirectional"))
    )
    (net (code "107") (name "/USART3_TX {slash} AF7") (class "Default")
      (node (ref "U1") (pin "69") (pinfunction "PD8_69") (pintype "bidirectional"))
    )
    (net (code "108") (name "/USART4_RX {slash} AF7") (class "Default")
      (node (ref "U1") (pin "84") (pinfunction "PC7_84") (pintype "bidirectional"))
    )
    (net (code "109") (name "/USART4_TX {slash} AF7") (class "Default")
      (node (ref "U1") (pin "83") (pinfunction "PC6_83") (pintype "bidirectional"))
    )
    (net (code "110") (name "/USBHS_DM {slash} SWDIO") (class "Default")
      (node (ref "CN1") (pin "7") (pinfunction "SWDIO_(PA13)_7") (pintype "passive"))
      (node (ref "U1") (pin "121") (pinfunction "PB9/USB2DM/SWDIO_121") (pintype "bidirectional"))
    )
    (net (code "111") (name "/USBHS_DP {slash} SWCLK") (class "Default")
      (node (ref "CN1") (pin "9") (pinfunction "SWCLK_(PA14)_9") (pintype "passive"))
      (node (ref "U1") (pin "120") (pinfunction "PB8/USB2DP/SWCLK_120") (pintype "bidirectional"))
    )
    (net (code "112") (name "/USBSS_RX_N") (class "Default")
      (node (ref "U1") (pin "126") (pinfunction "SSRXN_126") (pintype "bidirectional"))
    )
    (net (code "113") (name "/USBSS_RX_P") (class "Default")
      (node (ref "U1") (pin "127") (pinfunction "SSRXP_127") (pintype "bidirectional"))
    )
    (net (code "114") (name "/USBSS_TX_N") (class "Default")
      (node (ref "C14") (pin "2") (pinfunction "2_2") (pintype "passive"))
    )
    (net (code "115") (name "/USBSS_TX_P") (class "Default")
      (node (ref "C15") (pin "2") (pinfunction "2_2") (pintype "passive"))
    )
    (net (code "116") (name "/VBAT") (class "Default")
      (node (ref "C23") (pin "1") (pinfunction "1_1") (pintype "passive"))
      (node (ref "U1") (pin "7") (pinfunction "VBAT_7") (pintype "bidirectional"))
    )
    (net (code "117") (name "/Vbus_DET") (class "Default")
      (node (ref "U1") (pin "88") (pinfunction "PA9/OTG_VBUS_88") (pintype "bidirectional"))
    )
    (net (code "118") (name "/XI") (class "Default")
      (node (ref "C28") (pin "2") (pinfunction "2_2") (pintype "passive"))
      (node (ref "U1") (pin "23") (pinfunction "XI_23") (pintype "bidirectional"))
      (node (ref "Y1") (pin "1") (pinfunction "XTAL1_1") (pintype "passive"))
    )
    (net (code "119") (name "/XO") (class "Default")
      (node (ref "C27") (pin "2") (pinfunction "2_2") (pintype "passive"))
      (node (ref "U1") (pin "24") (pinfunction "XO_24") (pintype "bidirectional"))
      (node (ref "Y1") (pin "3") (pinfunction "XTAL2_3") (pintype "passive"))
    )
    (net (code "128") (name "1V2") (class "Default")
      (node (ref "C16") (pin "1") (pinfunction "1_1") (pintype "passive"))
      (node (ref "C17") (pin "1") (pinfunction "1_1") (pintype "passive"))
      (node (ref "C24") (pin "1") (pinfunction "1_1") (pintype "passive"))
      (node (ref "C25") (pin "2") (pinfunction "2_2") (pintype "passive"))
      (node (ref "C3") (pin "2") (pinfunction "2_2") (pintype "passive"))
      (node (ref "U1") (pin "11") (pinfunction "VDDK_11") (pintype "power_in"))
      (node (ref "U1") (pin "125") (pinfunction "VDD12A_125") (pintype "power_in"))
      (node (ref "U1") (pin "80") (pinfunction "VDDK_80") (pintype "power_in"))
    )
    (net (code "129") (name "3V3") (class "Default")
      (node (ref "C1") (pin "2") (pinfunction "2_2") (pintype "passive"))
      (node (ref "C10") (pin "2") (pinfunction "2_2") (pintype "passive"))
      (node (ref "C11") (pin "2") (pinfunction "2_2") (pintype "passive"))
      (node (ref "C12") (pin "1") (pinfunction "1_1") (pintype "passive"))
      (node (ref "C13") (pin "1") (pinfunction "1_1") (pintype "passive"))
      (node (ref "C18") (pin "1") (pinfunction "1_1") (pintype "passive"))
      (node (ref "C19") (pin "1") (pinfunction "1_1") (pintype "passive"))
      (node (ref "C2") (pin "2") (pinfunction "2_2") (pintype "passive"))
      (node (ref "C20") (pin "2") (pinfunction "2_2") (pintype "passive"))
      (node (ref "C21") (pin "1") (pinfunction "1_1") (pintype "passive"))
      (node (ref "C22") (pin "1") (pinfunction "1_1") (pintype "passive"))
      (node (ref "C29") (pin "1") (pinfunction "1_1") (pintype "passive"))
      (node (ref "C30") (pin "1") (pinfunction "1_1") (pintype "passive"))
      (node (ref "C4") (pin "2") (pinfunction "2_2") (pintype "passive"))
      (node (ref "C6") (pin "1") (pinfunction "1_1") (pintype "passive"))
      (node (ref "C7") (pin "2") (pinfunction "2_2") (pintype "passive"))
      (node (ref "C8") (pin "2") (pinfunction "2_2") (pintype "passive"))
      (node (ref "C9") (pin "1") (pinfunction "1_1") (pintype "passive"))
      (node (ref "J1") (pin "1") (pinfunction "1_1") (pintype "passive"))
      (node (ref "R1") (pin "2") (pinfunction "2_2") (pintype "passive"))
      (node (ref "R2") (pin "2") (pinfunction "2_2") (pintype "passive"))
      (node (ref "U1") (pin "105") (pinfunction "VIO18_105") (pintype "power_in"))
      (node (ref "U1") (pin "114") (pinfunction "VDDIO_114") (pintype "power_in"))
      (node (ref "U1") (pin "128") (pinfunction "VDD33_128") (pintype "power_in"))
      (node (ref "U1") (pin "16") (pinfunction "VDD33_16") (pintype "power_in"))
      (node (ref "U1") (pin "30") (pinfunction "VDDIO_30") (pintype "power_in"))
      (node (ref "U1") (pin "32") (pinfunction "VREFP_32") (pintype "bidirectional"))
      (node (ref "U1") (pin "33") (pinfunction "VDD33A_33") (pintype "power_in"))
      (node (ref "U1") (pin "38") (pinfunction "VDDIO_38") (pintype "power_in"))
      (node (ref "U1") (pin "51") (pinfunction "VDDIO_51") (pintype "power_in"))
      (node (ref "U1") (pin "6") (pinfunction "VDDIO_6") (pintype "power_in"))
      (node (ref "U1") (pin "63") (pinfunction "VIO18_63") (pintype "power_in"))
      (node (ref "U1") (pin "64") (pinfunction "VDDIO_64") (pintype "power_in"))
      (node (ref "U1") (pin "81") (pinfunction "VIO18_81") (pintype "power_in"))
      (node (ref "U1") (pin "82") (pinfunction "VDDIO_82") (pintype "power_in"))
      (node (ref "U1") (pin "93") (pinfunction "VDD33_93") (pintype "power_in"))
    )
    (net (code "130") (name "GND") (class "Default")
      (node (ref "C1") (pin "1") (pinfunction "1_1") (pintype "passive"))
      (node (ref "C10") (pin "1") (pinfunction "1_1") (pintype "passive"))
      (node (ref "C11") (pin "1") (pinfunction "1_1") (pintype "passive"))
      (node (ref "C12") (pin "2") (pinfunction "2_2") (pintype "passive"))
      (node (ref "C13") (pin "2") (pinfunction "2_2") (pintype "passive"))
      (node (ref "C16") (pin "2") (pinfunction "2_2") (pintype "passive"))
      (node (ref "C17") (pin "2") (pinfunction "2_2") (pintype "passive"))
      (node (ref "C18") (pin "2") (pinfunction "2_2") (pintype "passive"))
      (node (ref "C19") (pin "2") (pinfunction "2_2") (pintype "passive"))
      (node (ref "C2") (pin "1") (pinfunction "1_1") (pintype "passive"))
      (node (ref "C20") (pin "1") (pinfunction "1_1") (pintype "passive"))
      (node (ref "C21") (pin "2") (pinfunction "2_2") (pintype "passive"))
      (node (ref "C22") (pin "2") (pinfunction "2_2") (pintype "passive"))
      (node (ref "C23") (pin "2") (pinfunction "2_2") (pintype "passive"))
      (node (ref "C24") (pin "2") (pinfunction "2_2") (pintype "passive"))
      (node (ref "C25") (pin "1") (pinfunction "1_1") (pintype "passive"))
      (node (ref "C26") (pin "2") (pinfunction "2_2") (pintype "passive"))
      (node (ref "C27") (pin "1") (pinfunction "1_1") (pintype "passive"))
      (node (ref "C28") (pin "1") (pinfunction "1_1") (pintype "passive"))
      (node (ref "C29") (pin "2") (pinfunction "2_2") (pintype "passive"))
      (node (ref "C3") (pin "1") (pinfunction "1_1") (pintype "passive"))
      (node (ref "C30") (pin "2") (pinfunction "2_2") (pintype "passive"))
      (node (ref "C4") (pin "1") (pinfunction "1_1") (pintype "passive"))
      (node (ref "C5") (pin "1") (pinfunction "1_1") (pintype "passive"))
      (node (ref "C6") (pin "2") (pinfunction "2_2") (pintype "passive"))
      (node (ref "C7") (pin "1") (pinfunction "1_1") (pintype "passive"))
      (node (ref "C8") (pin "1") (pinfunction "1_1") (pintype "passive"))
      (node (ref "C9") (pin "2") (pinfunction "2_2") (pintype "passive"))
      (node (ref "CN1") (pin "5") (pinfunction "GND_5") (pintype "passive"))
      (node (ref "CN4") (pin "1") (pinfunction "1_1") (pintype "passive"))
      (node (ref "CN5") (pin "1") (pinfunction "1_1") (pintype "passive"))
      (node (ref "CN6") (pin "1") (pinfunction "1_1") (pintype "passive"))
      (node (ref "CN7") (pin "1") (pinfunction "1_1") (pintype "passive"))
      (node (ref "P1") (pin "1") (pinfunction "1_1") (pintype "passive"))
      (node (ref "P1") (pin "2") (pinfunction "2_2") (pintype "passive"))
      (node (ref "R3") (pin "2") (pinfunction "2_2") (pintype "passive"))
      (node (ref "R4") (pin "2") (pinfunction "2_2") (pintype "passive"))
      (node (ref "R5") (pin "2") (pinfunction "2_2") (pintype "passive"))
      (node (ref "R7") (pin "2") (pinfunction "2_2") (pintype "passive"))
      (node (ref "SW1") (pin "A1") (pinfunction "A1_A1") (pintype "passive"))
      (node (ref "SW1") (pin "A2") (pinfunction "A2_A2") (pintype "passive"))
      (node (ref "U1") (pin "0") (pinfunction "VSS_0") (pintype "power_in"))
      (node (ref "U1") (pin "122") (pinfunction "VSS_122") (pintype "power_in"))
      (node (ref "U1") (pin "22") (pinfunction "VSS_22") (pintype "power_in"))
      (node (ref "U1") (pin "31") (pinfunction "VSSA_31") (pintype "power_in"))
      (node (ref "Y1") (pin "2") (pinfunction "GND_2") (pintype "passive"))
      (node (ref "Y1") (pin "4") (pinfunction "GND_4") (pintype "passive"))
    )
    (net (code "131") (name "Net-(CN2-Pad1)") (class "Default")
      (node (ref "CN2") (pin "1") (pinfunction "1_1") (pintype "passive"))
      (node (ref "R2") (pin "1") (pinfunction "1_1") (pintype "passive"))
    )
    (net (code "132") (name "Net-(CN3-Pad2)") (class "Default")
      (node (ref "CN3") (pin "2") (pinfunction "2_2") (pintype "passive"))
      (node (ref "R3") (pin "1") (pinfunction "1_1") (pintype "passive"))
    )
    (net (code "133") (name "Net-(D2-Pad2)") (class "Default")
      (node (ref "D2") (pin "2") (pinfunction "2_2") (pintype "passive"))
      (node (ref "R4") (pin "1") (pinfunction "1_1") (pintype "passive"))
    )
    (net (code "134") (name "Net-(D3-Pad2)") (class "Default")
      (node (ref "D3") (pin "2") (pinfunction "2_2") (pintype "passive"))
      (node (ref "R5") (pin "1") (pinfunction "1_1") (pintype "passive"))
    )
    (net (code "135") (name "VBUS") (class "Default")
      (node (ref "D1") (pin "2") (pinfunction "K_2") (pintype "passive"))
      (node (ref "R6") (pin "2") (pinfunction "2_2") (pintype "passive"))
    )
    (net (code "136") (name "unconnected-(CN1-TDI_(PA15)-Pad4)") (class "Default")
      (node (ref "CN1") (pin "4") (pinfunction "TDI_(PA15)_4") (pintype "passive+no_connect"))
    )
    (net (code "137") (name "unconnected-(CN1-TDO_(PB3)-Pad6)") (class "Default")
      (node (ref "CN1") (pin "6") (pinfunction "TDO_(PB3)_6") (pintype "passive+no_connect"))
    )
    (net (code "138") (name "unconnected-(CN6-Pad4)") (class "Default")
      (node (ref "CN6") (pin "4") (pinfunction "4_4") (pintype "passive+no_connect"))
    )
    (net (code "139") (name "unconnected-(CN6-Pad6)") (class "Default")
      (node (ref "CN6") (pin "6") (pinfunction "6_6") (pintype "passive+no_connect"))
    )
  )
)
